# IFB-40004-R01_-_I2C_Toggle_Switch.net
KiCad netlist of a schematic drawn in EAGLE
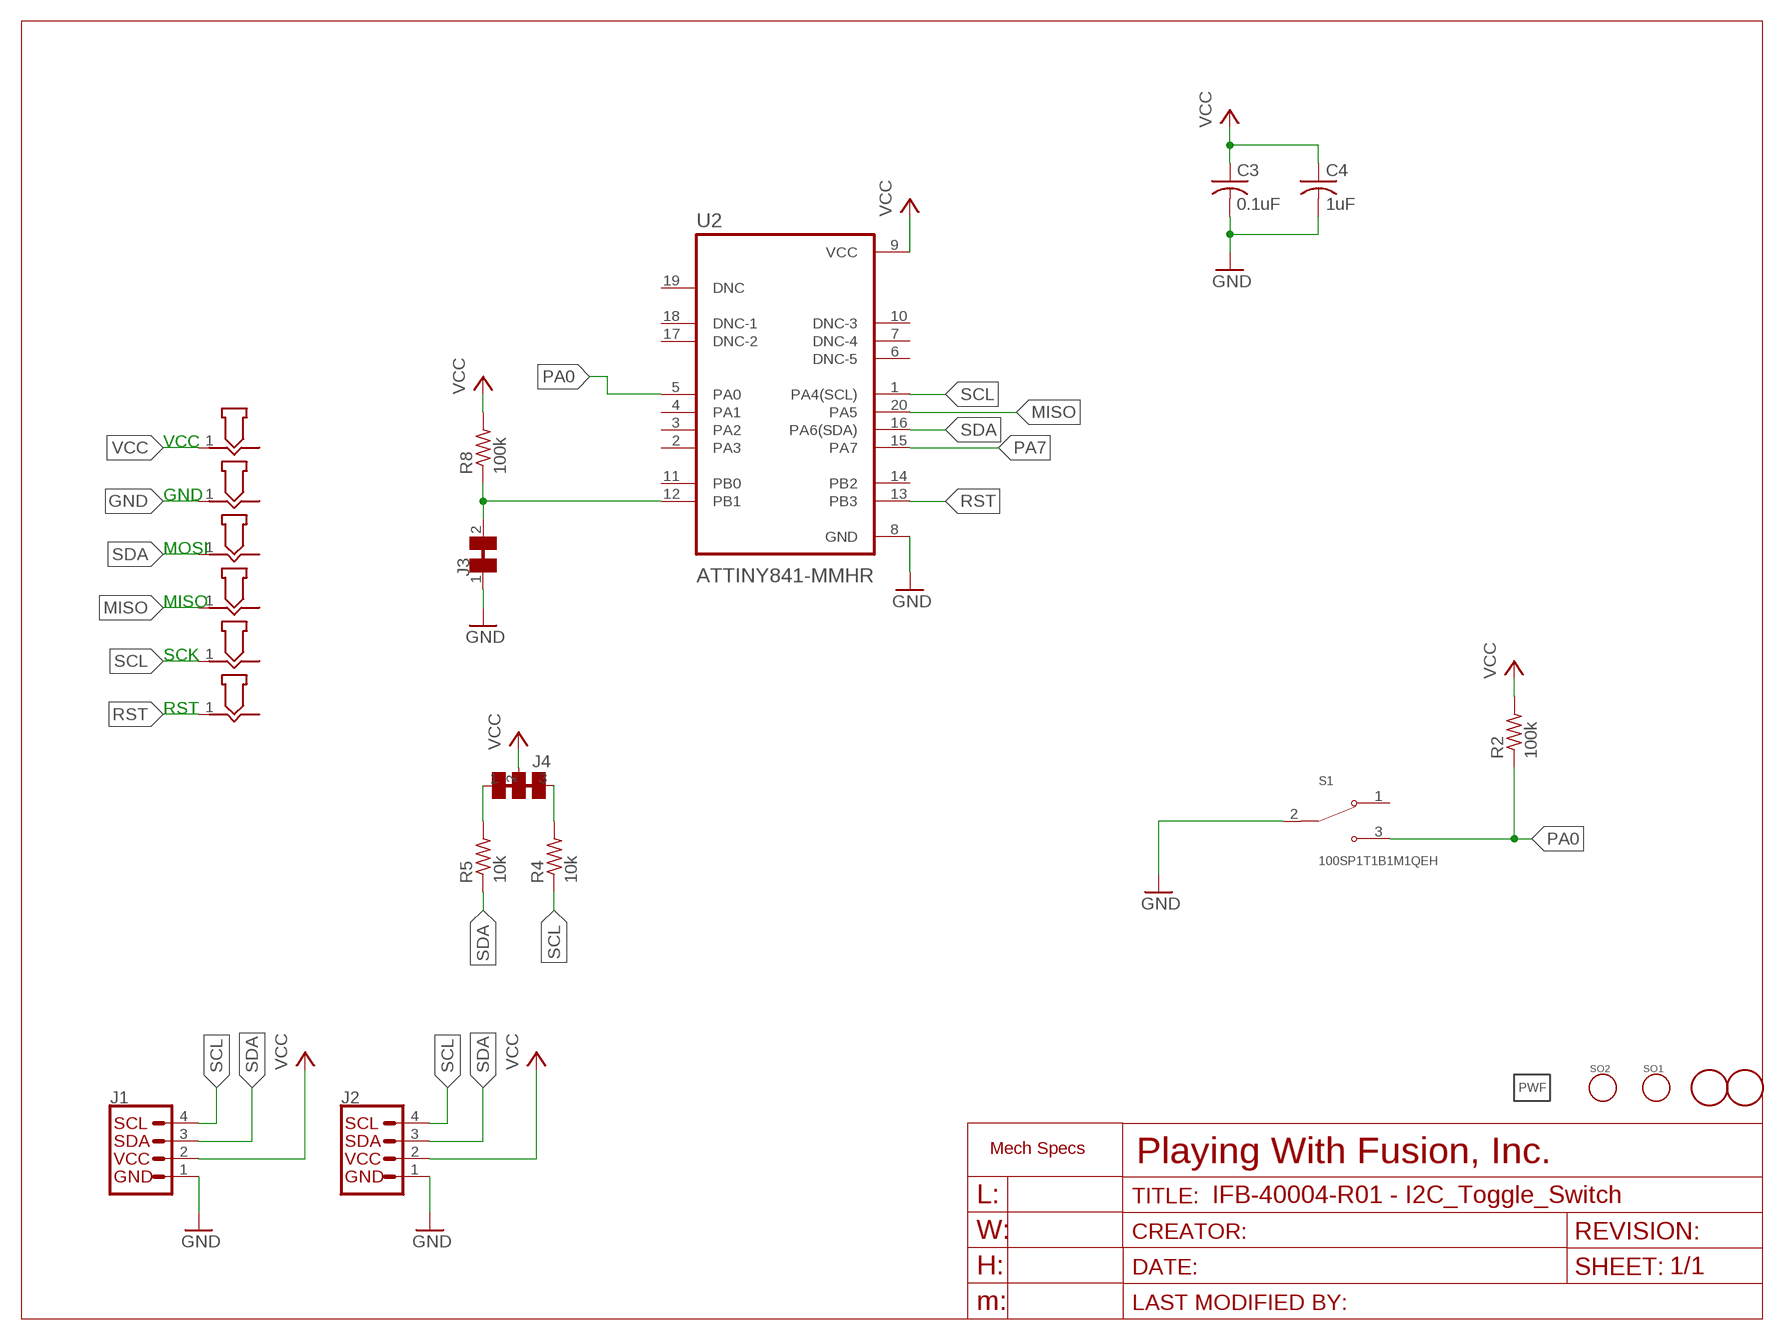
[diagram p0: schematic, sheet 1]

(export (version "E")
  (design (tool "Eeschema 10.0.6"))
  (components
    (comp (ref "C3")
      (value "0.1uF")
      (footprint "eagle-import:C0603K")
      (libsource (lib "eagle-import") (part "C-USC0603K"))
    )
    (comp (ref "C4")
      (value "1uF")
      (footprint "eagle-import:C0603K")
      (libsource (lib "eagle-import") (part "C-USC0603K"))
    )
    (comp (ref "GND")
      (value "POGO_PAD")
      (footprint "eagle-import:P50_POGO_BOARD_CONTACT_12MIL")
      (libsource (lib "eagle-import") (part "POGO_PAD"))
    )
    (comp (ref "J1")
      (value "QWIIC_CONNECTORJS-1MM")
      (footprint "eagle-import:1X04_1MM_RA")
      (libsource (lib "eagle-import") (part "QWIIC_CONNECTORJS-1MM"))
    )
    (comp (ref "J2")
      (value "QWIIC_CONNECTORJS-1MM")
      (footprint "eagle-import:1X04_1MM_RA")
      (libsource (lib "eagle-import") (part "QWIIC_CONNECTORJS-1MM"))
    )
    (comp (ref "J3")
      (value "CUTTABLE_JUMPER")
      (footprint "eagle-import:SMT_CUTTABLE_JUMPER")
      (libsource (lib "eagle-import") (part "CUTTABLE_JUMPER"))
    )
    (comp (ref "J4")
      (value "CUT_JUMPER_2X")
      (footprint "eagle-import:SMT_2X_CUTTABLE_JUMPER")
      (libsource (lib "eagle-import") (part "CUT_JUMPER_2X"))
    )
    (comp (ref "LOGO1")
      (value "PWF_LOGOPWF-5MM-SS")
      (footprint "eagle-import:LOGO_5MM_STEIN")
      (libsource (lib "eagle-import") (part "PWF_LOGOPWF-5MM-SS"))
    )
    (comp (ref "MISO")
      (value "POGO_PAD")
      (footprint "eagle-import:P50_POGO_BOARD_CONTACT_12MIL")
      (libsource (lib "eagle-import") (part "POGO_PAD"))
    )
    (comp (ref "MOSI")
      (value "POGO_PAD")
      (footprint "eagle-import:P50_POGO_BOARD_CONTACT_12MIL")
      (libsource (lib "eagle-import") (part "POGO_PAD"))
    )
    (comp (ref "R2")
      (value "100k")
      (footprint "eagle-import:R0603")
      (libsource (lib "eagle-import") (part "R-US_R0603"))
    )
    (comp (ref "R4")
      (value "10k")
      (footprint "eagle-import:R0603")
      (libsource (lib "eagle-import") (part "R-US_R0603"))
    )
    (comp (ref "R5")
      (value "10k")
      (footprint "eagle-import:R0603")
      (libsource (lib "eagle-import") (part "R-US_R0603"))
    )
    (comp (ref "R8")
      (value "100k")
      (footprint "eagle-import:R0603")
      (libsource (lib "eagle-import") (part "R-US_R0603"))
    )
    (comp (ref "RST")
      (value "POGO_PAD")
      (footprint "eagle-import:P50_POGO_BOARD_CONTACT_12MIL")
      (libsource (lib "eagle-import") (part "POGO_PAD"))
    )
    (comp (ref "S1")
      (value "100SP1T1B1M1QEH")
      (footprint "eagle-import:SW_100SP1T1B1M1QEH")
      (fields (field (name "MF") "E-Switch"))
      (libsource (lib "eagle-import") (part "100SP1T1B1M1QEH"))
    )
    (comp (ref "SCK")
      (value "POGO_PAD")
      (footprint "eagle-import:P50_POGO_BOARD_CONTACT_12MIL")
      (libsource (lib "eagle-import") (part "POGO_PAD"))
    )
    (comp (ref "SO1")
      (value "STAND_OFFNO4_TIGHT")
      (footprint "eagle-import:STANDOFF_NO4_TIGHT")
      (libsource (lib "eagle-import") (part "STAND_OFFNO4_TIGHT"))
    )
    (comp (ref "SO2")
      (value "STAND_OFFNO4_TIGHT")
      (footprint "eagle-import:STANDOFF_NO4_TIGHT")
      (libsource (lib "eagle-import") (part "STAND_OFFNO4_TIGHT"))
    )
    (comp (ref "U$2")
      (value "FIDUCIAL")
      (footprint "eagle-import:FIDUCIAL_1MM")
      (libsource (lib "eagle-import") (part "FIDUCIAL"))
    )
    (comp (ref "U$3")
      (value "FIDUCIAL")
      (footprint "eagle-import:FIDUCIAL_1MM")
      (libsource (lib "eagle-import") (part "FIDUCIAL"))
    )
    (comp (ref "U2")
      (value "ATTINY841-MMHR")
      (footprint "eagle-import:QFN45P300X300X85-21N")
      (fields (field (name "MF") "Microchip"))
      (libsource (lib "eagle-import") (part "ATTINY841-MMHR"))
    )
    (comp (ref "VCC")
      (value "POGO_PAD")
      (footprint "eagle-import:P50_POGO_BOARD_CONTACT_12MIL")
      (libsource (lib "eagle-import") (part "POGO_PAD"))
    )
  )
  (nets
    (net (code "1") (name "GND") (class "Default")
      (node (ref "C3") (pin "2") (pinfunction "2_2") (pintype "passive"))
      (node (ref "C4") (pin "2") (pinfunction "2_2") (pintype "passive"))
      (node (ref "GND") (pin "1") (pinfunction "P$1_1") (pintype "bidirectional"))
      (node (ref "J1") (pin "1") (pinfunction "GND_1") (pintype "power_in"))
      (node (ref "J2") (pin "1") (pinfunction "GND_1") (pintype "power_in"))
      (node (ref "J3") (pin "1") (pinfunction "1_1") (pintype "bidirectional"))
      (node (ref "S1") (pin "2") (pinfunction "2_2") (pintype "passive"))
      (node (ref "U2") (pin "8") (pinfunction "GND_8") (pintype "power_in"))
    )
    (net (code "2") (name "MISO") (class "Default")
      (node (ref "MISO") (pin "1") (pinfunction "P$1_1") (pintype "bidirectional"))
      (node (ref "U2") (pin "20") (pinfunction "PA5_20") (pintype "bidirectional"))
    )
    (net (code "3") (name "Net-(J4-Pad1)") (class "Default")
      (node (ref "J4") (pin "1") (pinfunction "1_1") (pintype "bidirectional"))
      (node (ref "R5") (pin "2") (pinfunction "2_2") (pintype "passive"))
    )
    (net (code "4") (name "Net-(J4-Pad3)") (class "Default")
      (node (ref "J4") (pin "3") (pinfunction "3_3") (pintype "bidirectional"))
      (node (ref "R4") (pin "2") (pinfunction "2_2") (pintype "passive"))
    )
    (net (code "5") (name "Net-(U2-PB1)") (class "Default")
      (node (ref "J3") (pin "2") (pinfunction "2_2") (pintype "bidirectional"))
      (node (ref "R8") (pin "1") (pinfunction "1_1") (pintype "passive"))
      (node (ref "U2") (pin "12") (pinfunction "PB1_12") (pintype "bidirectional"))
    )
    (net (code "6") (name "PA0") (class "Default")
      (node (ref "R2") (pin "1") (pinfunction "1_1") (pintype "passive"))
      (node (ref "S1") (pin "3") (pinfunction "3_3") (pintype "passive"))
      (node (ref "U2") (pin "5") (pinfunction "PA0_5") (pintype "bidirectional"))
    )
    (net (code "7") (name "PA7") (class "Default")
      (node (ref "U2") (pin "15") (pinfunction "PA7_15") (pintype "bidirectional"))
    )
    (net (code "8") (name "RST") (class "Default")
      (node (ref "RST") (pin "1") (pinfunction "P$1_1") (pintype "bidirectional"))
      (node (ref "U2") (pin "13") (pinfunction "PB3_13") (pintype "bidirectional"))
    )
    (net (code "9") (name "SCL") (class "Default")
      (node (ref "J1") (pin "4") (pinfunction "SCL_4") (pintype "passive"))
      (node (ref "J2") (pin "4") (pinfunction "SCL_4") (pintype "passive"))
      (node (ref "R4") (pin "1") (pinfunction "1_1") (pintype "passive"))
      (node (ref "SCK") (pin "1") (pinfunction "P$1_1") (pintype "bidirectional"))
      (node (ref "U2") (pin "1") (pinfunction "PA4(SCL)_1") (pintype "bidirectional"))
    )
    (net (code "10") (name "SDA") (class "Default")
      (node (ref "J1") (pin "3") (pinfunction "SDA_3") (pintype "passive"))
      (node (ref "J2") (pin "3") (pinfunction "SDA_3") (pintype "passive"))
      (node (ref "MOSI") (pin "1") (pinfunction "P$1_1") (pintype "bidirectional"))
      (node (ref "R5") (pin "1") (pinfunction "1_1") (pintype "passive"))
      (node (ref "U2") (pin "16") (pinfunction "PA6(SDA)_16") (pintype "bidirectional"))
    )
    (net (code "11") (name "VCC") (class "Default")
      (node (ref "C3") (pin "1") (pinfunction "1_1") (pintype "passive"))
      (node (ref "C4") (pin "1") (pinfunction "1_1") (pintype "passive"))
      (node (ref "J1") (pin "2") (pinfunction "VCC_2") (pintype "power_in"))
      (node (ref "J2") (pin "2") (pinfunction "VCC_2") (pintype "power_in"))
      (node (ref "J4") (pin "2") (pinfunction "2_2") (pintype "bidirectional"))
      (node (ref "R2") (pin "2") (pinfunction "2_2") (pintype "passive"))
      (node (ref "R8") (pin "2") (pinfunction "2_2") (pintype "passive"))
      (node (ref "U2") (pin "9") (pinfunction "VCC_9") (pintype "power_in"))
      (node (ref "VCC") (pin "1") (pinfunction "P$1_1") (pintype "bidirectional"))
    )
    (net (code "12") (name "unconnected-(S1-Pad1)") (class "Default")
      (node (ref "S1") (pin "1") (pinfunction "1_1") (pintype "passive"))
    )
    (net (code "13") (name "unconnected-(U2-DNC-1-Pad18)") (class "Default")
      (node (ref "U2") (pin "18") (pinfunction "DNC-1_18") (pintype "bidirectional"))
    )
    (net (code "14") (name "unconnected-(U2-DNC-2-Pad17)") (class "Default")
      (node (ref "U2") (pin "17") (pinfunction "DNC-2_17") (pintype "bidirectional"))
    )
    (net (code "15") (name "unconnected-(U2-DNC-3-Pad10)") (class "Default")
      (node (ref "U2") (pin "10") (pinfunction "DNC-3_10") (pintype "bidirectional"))
    )
    (net (code "16") (name "unconnected-(U2-DNC-4-Pad7)") (class "Default")
      (node (ref "U2") (pin "7") (pinfunction "DNC-4_7") (pintype "bidirectional"))
    )
    (net (code "17") (name "unconnected-(U2-DNC-5-Pad6)") (class "Default")
      (node (ref "U2") (pin "6") (pinfunction "DNC-5_6") (pintype "bidirectional"))
    )
    (net (code "18") (name "unconnected-(U2-DNC-Pad19)") (class "Default")
      (node (ref "U2") (pin "19") (pinfunction "DNC_19") (pintype "bidirectional"))
    )
    (net (code "19") (name "unconnected-(U2-PA1-Pad4)") (class "Default")
      (node (ref "U2") (pin "4") (pinfunction "PA1_4") (pintype "bidirectional"))
    )
    (net (code "20") (name "unconnected-(U2-PA2-Pad3)") (class "Default")
      (node (ref "U2") (pin "3") (pinfunction "PA2_3") (pintype "bidirectional"))
    )
    (net (code "21") (name "unconnected-(U2-PA3-Pad2)") (class "Default")
      (node (ref "U2") (pin "2") (pinfunction "PA3_2") (pintype "bidirectional"))
    )
    (net (code "22") (name "unconnected-(U2-PB0-Pad11)") (class "Default")
      (node (ref "U2") (pin "11") (pinfunction "PB0_11") (pintype "bidirectional"))
    )
    (net (code "23") (name "unconnected-(U2-PB2-Pad14)") (class "Default")
      (node (ref "U2") (pin "14") (pinfunction "PB2_14") (pintype "bidirectional"))
    )
  )
)
